# Assignment.net
KiCad netlist of a schematic drawn in EAGLE
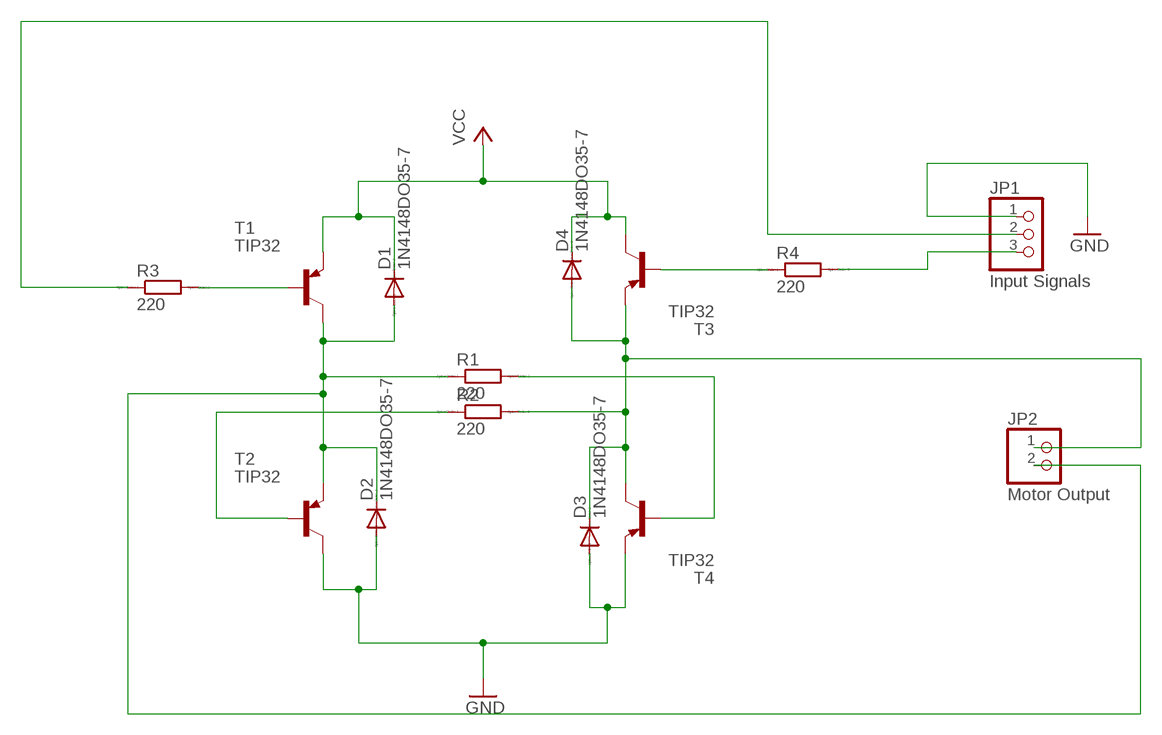
[diagram p0: schematic, sheet 1]

(export (version "E")
  (design (tool "Eeschema 10.0.6"))
  (components
    (comp (ref "D1")
      (value "1N4148DO35-7")
      (footprint "eagle-import:DO35-7")
      (libsource (lib "eagle-import") (part "1N4148DO35-7"))
    )
    (comp (ref "D2")
      (value "1N4148DO35-7")
      (footprint "eagle-import:DO35-7")
      (libsource (lib "eagle-import") (part "1N4148DO35-7"))
    )
    (comp (ref "D3")
      (value "1N4148DO35-7")
      (footprint "eagle-import:DO35-7")
      (libsource (lib "eagle-import") (part "1N4148DO35-7"))
    )
    (comp (ref "D4")
      (value "1N4148DO35-7")
      (footprint "eagle-import:DO35-7")
      (libsource (lib "eagle-import") (part "1N4148DO35-7"))
    )
    (comp (ref "JP1")
      (value "Input Signals")
      (footprint "eagle-import:1X03")
      (libsource (lib "eagle-import") (part "PINHD-1X3"))
    )
    (comp (ref "JP2")
      (value "Motor Output")
      (footprint "eagle-import:1X02")
      (libsource (lib "eagle-import") (part "PINHD-1X2"))
    )
    (comp (ref "R1")
      (value "220")
      (footprint "eagle-import:0204_7")
      (libsource (lib "eagle-import") (part "R0204/7"))
    )
    (comp (ref "R2")
      (value "220")
      (footprint "eagle-import:0204_7")
      (libsource (lib "eagle-import") (part "R0204/7"))
    )
    (comp (ref "R3")
      (value "220")
      (footprint "eagle-import:0204_7")
      (libsource (lib "eagle-import") (part "R0204/7"))
    )
    (comp (ref "R4")
      (value "220")
      (footprint "eagle-import:0204_7")
      (libsource (lib "eagle-import") (part "R0204/7"))
    )
    (comp (ref "T1")
      (value "TIP32")
      (footprint "eagle-import:TO220")
      (libsource (lib "eagle-import") (part "TIP32"))
    )
    (comp (ref "T2")
      (value "TIP32")
      (footprint "eagle-import:TO220")
      (libsource (lib "eagle-import") (part "TIP32"))
    )
    (comp (ref "T3")
      (value "TIP32")
      (footprint "eagle-import:TO220")
      (libsource (lib "eagle-import") (part "TIP32"))
    )
    (comp (ref "T4")
      (value "TIP32")
      (footprint "eagle-import:TO220")
      (libsource (lib "eagle-import") (part "TIP32"))
    )
  )
  (nets
    (net (code "1") (name "GND") (class "Default")
      (node (ref "D2") (pin "A") (pinfunction "A_A") (pintype "passive"))
      (node (ref "D3") (pin "A") (pinfunction "A_A") (pintype "passive"))
      (node (ref "JP1") (pin "1") (pinfunction "1_1") (pintype "passive"))
      (node (ref "T2") (pin "2") (pinfunction "C_2") (pintype "passive"))
      (node (ref "T4") (pin "3") (pinfunction "E_3") (pintype "passive"))
    )
    (net (code "2") (name "Net-(JP1-Pad2)") (class "Default")
      (node (ref "JP1") (pin "2") (pinfunction "2_2") (pintype "passive"))
      (node (ref "R3") (pin "1") (pinfunction "1_1") (pintype "passive"))
    )
    (net (code "3") (name "Net-(JP1-Pad3)") (class "Default")
      (node (ref "JP1") (pin "3") (pinfunction "3_3") (pintype "passive"))
      (node (ref "R4") (pin "2") (pinfunction "2_2") (pintype "passive"))
    )
    (net (code "4") (name "Net-(T1-B)") (class "Default")
      (node (ref "R3") (pin "2") (pinfunction "2_2") (pintype "passive"))
      (node (ref "T1") (pin "1") (pinfunction "B_1") (pintype "passive"))
    )
    (net (code "5") (name "Net-(T1-C)") (class "Default")
      (node (ref "D1") (pin "A") (pinfunction "A_A") (pintype "passive"))
      (node (ref "D2") (pin "C") (pinfunction "C_C") (pintype "passive"))
      (node (ref "JP2") (pin "2") (pinfunction "2_2") (pintype "passive"))
      (node (ref "R1") (pin "1") (pinfunction "1_1") (pintype "passive"))
      (node (ref "T1") (pin "2") (pinfunction "C_2") (pintype "passive"))
      (node (ref "T2") (pin "3") (pinfunction "E_3") (pintype "passive"))
    )
    (net (code "6") (name "Net-(T2-B)") (class "Default")
      (node (ref "R2") (pin "1") (pinfunction "1_1") (pintype "passive"))
      (node (ref "T2") (pin "1") (pinfunction "B_1") (pintype "passive"))
    )
    (net (code "7") (name "Net-(T3-B)") (class "Default")
      (node (ref "R4") (pin "1") (pinfunction "1_1") (pintype "passive"))
      (node (ref "T3") (pin "1") (pinfunction "B_1") (pintype "passive"))
    )
    (net (code "8") (name "Net-(T3-E)") (class "Default")
      (node (ref "D3") (pin "C") (pinfunction "C_C") (pintype "passive"))
      (node (ref "D4") (pin "A") (pinfunction "A_A") (pintype "passive"))
      (node (ref "JP2") (pin "1") (pinfunction "1_1") (pintype "passive"))
      (node (ref "R2") (pin "2") (pinfunction "2_2") (pintype "passive"))
      (node (ref "T3") (pin "3") (pinfunction "E_3") (pintype "passive"))
      (node (ref "T4") (pin "2") (pinfunction "C_2") (pintype "passive"))
    )
    (net (code "9") (name "Net-(T4-B)") (class "Default")
      (node (ref "R1") (pin "2") (pinfunction "2_2") (pintype "passive"))
      (node (ref "T4") (pin "1") (pinfunction "B_1") (pintype "passive"))
    )
    (net (code "10") (name "VCC") (class "Default")
      (node (ref "D1") (pin "C") (pinfunction "C_C") (pintype "passive"))
      (node (ref "D4") (pin "C") (pinfunction "C_C") (pintype "passive"))
      (node (ref "T1") (pin "3") (pinfunction "E_3") (pintype "passive"))
      (node (ref "T3") (pin "2") (pinfunction "C_2") (pintype "passive"))
    )
  )
)
